# PowerRegulator.net
KiCad netlist of a schematic drawn in Altium Designer
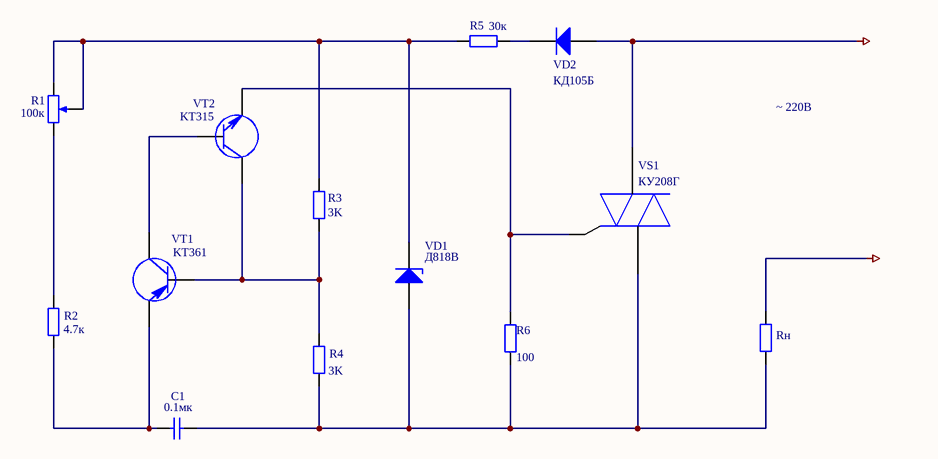
[diagram p0: PowerRegulator.SchDoc]

(export (version "E")
  (design (tool "Eeschema 10.0.6"))
  (components
    (comp (ref "C1")
      (value "0.1мк")
      (footprint "RAD-0.3")
      (description "Capacitor")
      (fields (field (name "Comment") "Cap") (field (name "PUBLISHER") "Altium Limited"))
      (libsource (lib "Miscellaneous Devices") (part "Cap"))
    )
    (comp (ref "R1")
      (value "100к")
      (footprint "VR5")
      (description "Potentiometer")
      (fields (field (name "Comment") "RPot") (field (name "PUBLISHER") "Altium Limited"))
      (libsource (lib "ForScheme") (part "RPot"))
    )
    (comp (ref "R2")
      (value "4.7к")
      (footprint "AXIAL-0.4")
      (description "Resistor")
      (fields (field (name "Comment") "Res2") (field (name "PUBLISHER") "Altium Limited"))
      (libsource (lib "Miscellaneous Devices") (part "Res2"))
    )
    (comp (ref "R3")
      (value "3K")
      (footprint "AXIAL-0.4")
      (description "Resistor")
      (fields (field (name "Comment") "Res2") (field (name "PUBLISHER") "Altium Limited"))
      (libsource (lib "Miscellaneous Devices") (part "Res2"))
    )
    (comp (ref "R4")
      (value "3K")
      (footprint "AXIAL-0.4")
      (description "Resistor")
      (fields (field (name "Comment") "Res2") (field (name "PUBLISHER") "Altium Limited"))
      (libsource (lib "Miscellaneous Devices") (part "Res2"))
    )
    (comp (ref "R5")
      (value "30к")
      (footprint "AXIAL-0.4")
      (description "Resistor")
      (fields (field (name "Comment") "Res2") (field (name "PUBLISHER") "Altium Limited"))
      (libsource (lib "") (part "Res2_1"))
    )
    (comp (ref "R6")
      (value "100")
      (footprint "AXIAL-0.4")
      (description "Resistor")
      (fields (field (name "Comment") "Res2") (field (name "PUBLISHER") "Altium Limited"))
      (libsource (lib "Miscellaneous Devices") (part "Res2"))
    )
    (comp (ref "Rн")
      (value "Res2")
      (footprint "AXIAL-0.4")
      (description "Resistor")
      (fields (field (name "PUBLISHER") "Altium Limited"))
      (libsource (lib "Miscellaneous Devices") (part "Res2"))
    )
    (comp (ref "VD1")
      (value "Д818В")
      (footprint "DIODE-0.7")
      (description "Zener Diode")
      (fields (field (name "PUBLISHER") "Altium Limited"))
      (libsource (lib "ForScheme") (part "D Zener"))
    )
    (comp (ref "VD2")
      (value "КД105Б")
      (footprint "SMC")
      (description "Default Diode")
      (fields (field (name "PUBLISHER") "Altium Limited"))
      (libsource (lib "Miscellaneous Devices") (part "Diode"))
    )
    (comp (ref "VS1")
      (value "КУ208Г")
      (description "Generic thyristor")
      (libsource (lib "ForScheme") (part "Thyristor"))
    )
    (comp (ref "VT1")
      (value "KT361")
      (footprint "SOT-23B_N")
      (description "PNP Bipolar Transistor")
      (fields (field (name "PUBLISHER") "Altium Limited"))
      (libsource (lib "ForScheme") (part "PNP"))
    )
    (comp (ref "VT2")
      (value "KT315")
      (footprint "TO-226-AA")
      (description "NPN Bipolar Transistor")
      (fields (field (name "PUBLISHER") "Altium Limited"))
      (libsource (lib "ForScheme") (part "NPN"))
    )
  )
  (nets
    (net (code "1") (name "GND") (class "Default")
      (node (ref "Rн") (pin "2") (pinfunction "2_2") (pintype "passive"))
      (node (ref "VD2") (pin "1") (pinfunction "A_1") (pintype "passive"))
      (node (ref "VS1") (pin "1") (pinfunction "1_1") (pintype "passive"))
    )
    (net (code "2") (name "Net-(R1-BOT)") (class "Default")
      (node (ref "R1") (pin "2") (pinfunction "BOT_2") (pintype "passive"))
      (node (ref "R1") (pin "3") (pinfunction "TAP_3") (pintype "passive"))
      (node (ref "R3") (pin "2") (pinfunction "2_2") (pintype "passive"))
      (node (ref "R5") (pin "2") (pinfunction "2_2") (pintype "passive"))
      (node (ref "VD1") (pin "2") (pinfunction "K_2") (pintype "passive"))
    )
    (net (code "3") (name "Net-(R1-TOP)") (class "Default")
      (node (ref "R1") (pin "1") (pinfunction "TOP_1") (pintype "passive"))
      (node (ref "R2") (pin "2") (pinfunction "2_2") (pintype "passive"))
    )
    (net (code "4") (name "Net-(VD1-A)") (class "Default")
      (node (ref "C1") (pin "2") (pinfunction "2_2") (pintype "passive"))
      (node (ref "R4") (pin "1") (pinfunction "1_1") (pintype "passive"))
      (node (ref "R6") (pin "1") (pinfunction "1_1") (pintype "passive"))
      (node (ref "Rн") (pin "1") (pinfunction "1_1") (pintype "passive"))
      (node (ref "VD1") (pin "1") (pinfunction "A_1") (pintype "passive"))
      (node (ref "VS1") (pin "2") (pinfunction "2_2") (pintype "passive"))
    )
    (net (code "5") (name "Net-(VD2-K)") (class "Default")
      (node (ref "R5") (pin "1") (pinfunction "1_1") (pintype "passive"))
      (node (ref "VD2") (pin "2") (pinfunction "K_2") (pintype "passive"))
    )
    (net (code "6") (name "Net-(VT1-B)") (class "Default")
      (node (ref "R3") (pin "1") (pinfunction "1_1") (pintype "passive"))
      (node (ref "R4") (pin "2") (pinfunction "2_2") (pintype "passive"))
      (node (ref "VT1") (pin "2") (pinfunction "B_2") (pintype "passive"))
      (node (ref "VT2") (pin "3") (pinfunction "E_3") (pintype "passive"))
    )
    (net (code "7") (name "Net-(VT1-C)") (class "Default")
      (node (ref "C1") (pin "1") (pinfunction "1_1") (pintype "passive"))
      (node (ref "R2") (pin "1") (pinfunction "1_1") (pintype "passive"))
      (node (ref "VT1") (pin "1") (pinfunction "C_1") (pintype "passive"))
    )
    (net (code "8") (name "Net-(VT1-E)") (class "Default")
      (node (ref "VT1") (pin "3") (pinfunction "E_3") (pintype "passive"))
      (node (ref "VT2") (pin "2") (pinfunction "B_2") (pintype "passive"))
    )
    (net (code "9") (name "Net-(VT2-C)") (class "Default")
      (node (ref "R6") (pin "2") (pinfunction "2_2") (pintype "passive"))
      (node (ref "VS1") (pin "3") (pinfunction "3_3") (pintype "passive"))
      (node (ref "VT2") (pin "1") (pinfunction "C_1") (pintype "passive"))
    )
  )
)
